# MCU.net
KiCad netlist of a schematic drawn in Altium Designer
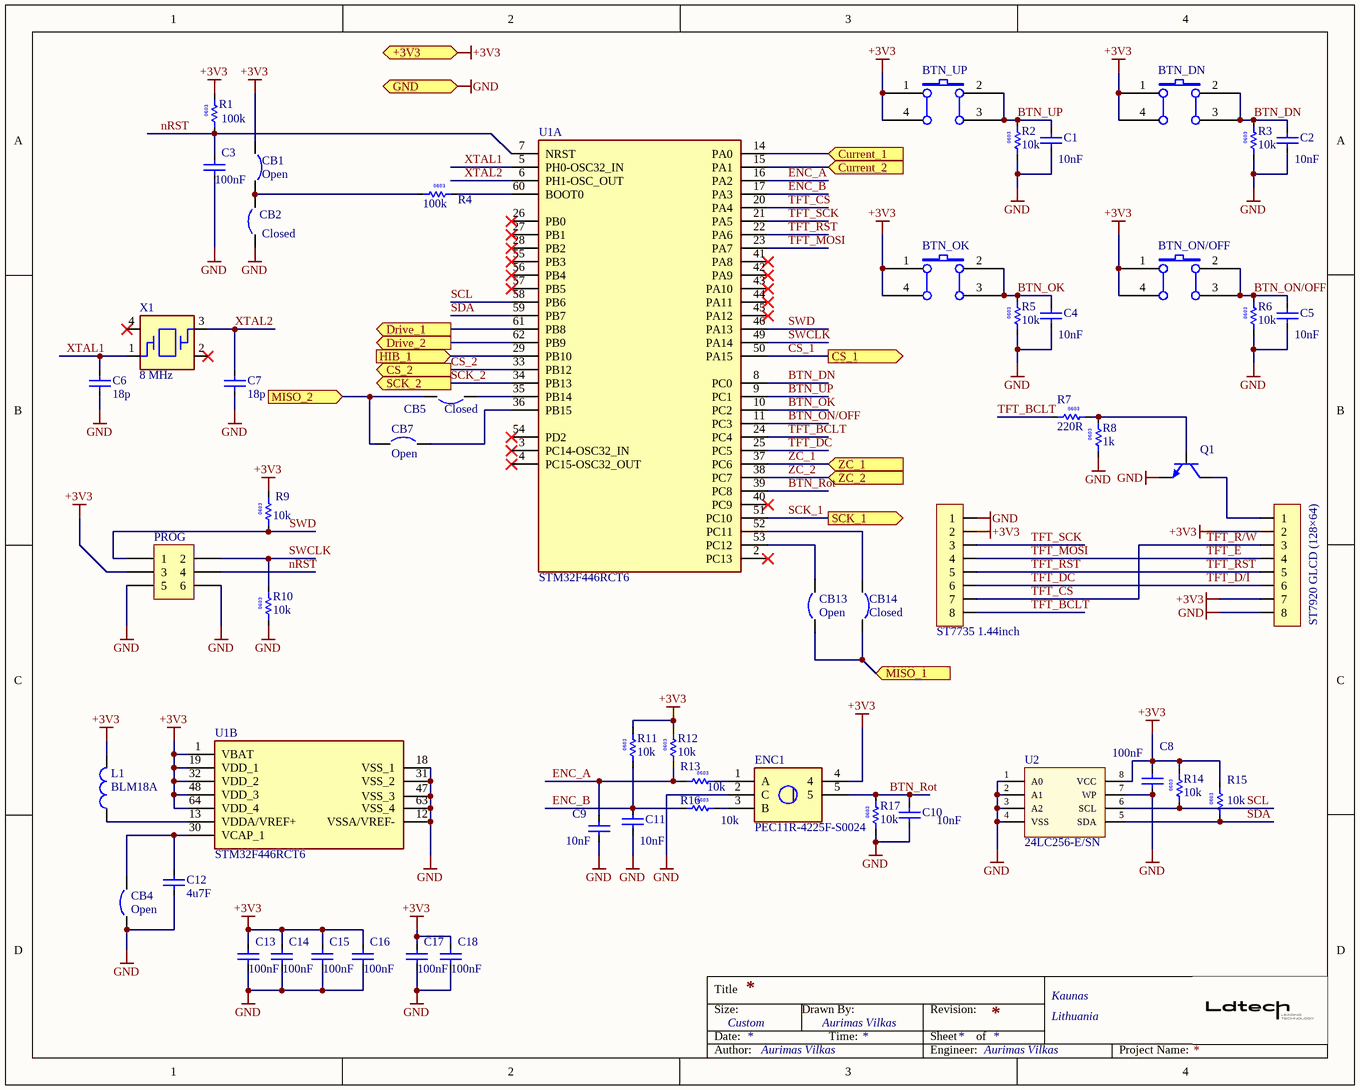
[diagram p0: MCU.SchDoc]

(export (version "E")
  (design (tool "Eeschema 10.0.6"))
  (components
    (comp (ref "BTN_DN")
      (value "Button")
      (footprint "PB-6X6mm")
      (description "FSM2JRT -  Tactile Switch, Non Illuminated, 24 V, 50 mA, 225 gf, PC Pin, FSM Series")
      (libsource (lib "AV_Lib_200418") (part "Tactile PB"))
    )
    (comp (ref "BTN_OK")
      (value "Button")
      (footprint "PB-6X6mm")
      (description "FSM2JRT -  Tactile Switch, Non Illuminated, 24 V, 50 mA, 225 gf, PC Pin, FSM Series")
      (libsource (lib "AV_Lib_200418") (part "Tactile PB"))
    )
    (comp (ref "BTN_ON/OFF")
      (value "Button")
      (footprint "PB-6X6mm")
      (description "FSM2JRT -  Tactile Switch, Non Illuminated, 24 V, 50 mA, 225 gf, PC Pin, FSM Series")
      (libsource (lib "AV_Lib_200418") (part "Tactile PB"))
    )
    (comp (ref "BTN_UP")
      (value "Button")
      (footprint "PB-6X6mm")
      (description "FSM2JRT -  Tactile Switch, Non Illuminated, 24 V, 50 mA, 225 gf, PC Pin, FSM Series")
      (libsource (lib "AV_Lib_200418") (part "Tactile PB"))
    )
    (comp (ref "C1") (value "10nF") (footprint "CAPC1608N") (libsource (lib "DB") (part "C_SM")))
    (comp (ref "C2") (value "10nF") (footprint "CAPC1608N") (libsource (lib "DB") (part "C_SM")))
    (comp (ref "C3") (value "100nF") (footprint "CAPC1608N") (libsource (lib "DB") (part "C_SM")))
    (comp (ref "C4") (value "10nF") (footprint "CAPC1608N") (libsource (lib "DB") (part "C_SM")))
    (comp (ref "C5") (value "10nF") (footprint "CAPC1608N") (libsource (lib "DB") (part "C_SM")))
    (comp (ref "C6") (value "18p") (footprint "CAPC1608N") (libsource (lib "DB") (part "C_SM")))
    (comp (ref "C7") (value "18p") (footprint "CAPC1608N") (libsource (lib "DB") (part "C_SM")))
    (comp (ref "C8") (value "100nF") (footprint "CAPC1608N") (libsource (lib "DB") (part "C_SM")))
    (comp (ref "C9") (value "10nF") (footprint "CAPC1608N") (libsource (lib "DB") (part "C_SM")))
    (comp (ref "C10") (value "10nF") (footprint "CAPC1608N") (libsource (lib "DB") (part "C_SM")))
    (comp (ref "C11") (value "10nF") (footprint "CAPC1608N") (libsource (lib "DB") (part "C_SM")))
    (comp (ref "C12") (value "4u7F") (footprint "CAPC1608N") (libsource (lib "DB") (part "C_SM")))
    (comp (ref "C13") (value "100nF") (footprint "CAPC1608N") (libsource (lib "DB") (part "C_SM")))
    (comp (ref "C14") (value "100nF") (footprint "CAPC1608N") (libsource (lib "DB") (part "C_SM")))
    (comp (ref "C15") (value "100nF") (footprint "CAPC1608N") (libsource (lib "DB") (part "C_SM")))
    (comp (ref "C16") (value "100nF") (footprint "CAPC1608N") (libsource (lib "DB") (part "C_SM")))
    (comp (ref "C17") (value "100nF") (footprint "CAPC1608N") (libsource (lib "DB") (part "C_SM")))
    (comp (ref "C18") (value "100nF") (footprint "CAPC1608N") (libsource (lib "DB") (part "C_SM")))
    (comp (ref "CB1")
      (value "Open")
      (footprint "CB_0603")
      (description "Circuit Breaker")
      (libsource (lib "AV_Lib_200418") (part "CB Open"))
    )
    (comp (ref "CB2")
      (value "Closed")
      (footprint "CB_0603")
      (description "Circuit Breaker")
      (libsource (lib "AV_Lib_200418") (part "CB Closed"))
    )
    (comp (ref "CB4")
      (value "Open")
      (footprint "CB_0603")
      (description "Circuit Breaker")
      (libsource (lib "AV_Lib_200418") (part "CB Open"))
    )
    (comp (ref "CB5")
      (value "Closed")
      (footprint "CB_0603")
      (description "Circuit Breaker")
      (libsource (lib "AV_Lib_200418") (part "CB Closed"))
    )
    (comp (ref "CB7")
      (value "Open")
      (footprint "CB_0603")
      (description "Circuit Breaker")
      (libsource (lib "AV_Lib_200418") (part "CB Open"))
    )
    (comp (ref "CB13")
      (value "Open")
      (footprint "CB_0603")
      (description "Circuit Breaker")
      (libsource (lib "AV_Lib_200418") (part "CB Open"))
    )
    (comp (ref "CB14")
      (value "Closed")
      (footprint "CB_0603")
      (description "Circuit Breaker")
      (libsource (lib "AV_Lib_200418") (part "CB Closed"))
    )
    (comp (ref "ENC1")
      (value "PEC11R-4225F-S0024")
      (footprint "PEC12R-4XXXF-SXXXX_1")
      (libsource (lib "AV_Lib_200418") (part "PEC11R-4225F-S0024"))
    )
    (comp (ref "L1")
      (value "BLM18A")
      (footprint "0603L")
      (libsource (lib "AV_Lib_200418") (part "BLM18AG601SN1D"))
    )
    (comp (ref "PROG")
      (value "PROG")
      (footprint "B6B_SMT")
      (libsource (lib "AV_Lib_200418") (part "B6B_SMT"))
    )
    (comp (ref "Q1")
      (value "FMMT493ATA")
      (footprint "SOT23-3")
      (description "FMMT493ATA -  Bipolar (BJT) Single Transistor, NPN, 60 V, 150 MHz, 500 mW, 1 A, 300 hFE")
      (libsource (lib "AV_Lib_200418") (part "FMMT493ATA"))
    )
    (comp (ref "R1") (value "100k") (footprint "RESC1608N") (libsource (lib "DB") (part "R0603")))
    (comp (ref "R2") (value "10k") (footprint "RESC1608N") (libsource (lib "DB") (part "R0603")))
    (comp (ref "R3") (value "10k") (footprint "RESC1608N") (libsource (lib "DB") (part "R0603")))
    (comp (ref "R4") (value "100k") (footprint "RESC1608N") (libsource (lib "DB") (part "R0603")))
    (comp (ref "R5") (value "10k") (footprint "RESC1608N") (libsource (lib "DB") (part "R0603")))
    (comp (ref "R6") (value "10k") (footprint "RESC1608N") (libsource (lib "DB") (part "R0603")))
    (comp (ref "R7") (value "220R") (footprint "RESC1608N") (libsource (lib "DB") (part "R0603")))
    (comp (ref "R8") (value "1k") (footprint "RESC1608N") (libsource (lib "DB") (part "R0603")))
    (comp (ref "R9") (value "10k") (footprint "RESC1608N") (libsource (lib "DB") (part "R0603")))
    (comp (ref "R10") (value "10k") (footprint "RESC1608N") (libsource (lib "DB") (part "R0603")))
    (comp (ref "R11") (value "10k") (footprint "RESC1608N") (libsource (lib "DB") (part "R0603")))
    (comp (ref "R12") (value "10k") (footprint "RESC1608N") (libsource (lib "DB") (part "R0603")))
    (comp (ref "R13") (value "10k") (footprint "RESC1608N") (libsource (lib "DB") (part "R0603")))
    (comp (ref "R14") (value "10k") (footprint "RESC1608N") (libsource (lib "DB") (part "R0603")))
    (comp (ref "R15") (value "10k") (footprint "RESC1608N") (libsource (lib "DB") (part "R0603")))
    (comp (ref "R16") (value "10k") (footprint "RESC1608N") (libsource (lib "DB") (part "R0603")))
    (comp (ref "R17") (value "10k") (footprint "RESC1608N") (libsource (lib "DB") (part "R0603")))
    (comp (ref "ST7735 1.44inch")
      (value "ST7735 1.44inch")
      (footprint "B8B-XH-A (LF)(SN)")
      (libsource (lib "") (part "B8B-XH-A_1"))
    )
    (comp (ref "ST7920 GLCD (128×64)")
      (value "ST7920 GLCD (128×64)")
      (footprint "B8B-XH-A (LF)(SN)")
      (libsource (lib "AV_Lib_200418") (part "B8B-XH-A"))
    )
    (comp (ref "U1")
      (value "STM32F446RCT6")
      (footprint "LQFP-64N")
      (libsource (lib "AV_Lib_200418") (part "STM32F446RCT6TR"))
    )
    (comp (ref "U2")
      (value "24LC256-E/SN")
      (footprint "SOIC-8")
      (description "24LC256-E/SN -  EEPROM, 256 Kbit, 32K x 8bit, Serial I2C (2-Wire), 400 kHz, SOIC, 8 Pins")
      (libsource (lib "AV_Lib_200418") (part "24LC256-E/SN"))
    )
    (comp (ref "X1")
      (value "8 MHz")
      (footprint "2SMX-3SMXB")
      (description "CRYSTAL, 8M, 18PF CL, 6X3.6MM SMT")
      (libsource (lib "DB") (part "XTAL2"))
    )
  )
  (nets
    (net (code "1") (name "+3V3") (class "Default")
      (node (ref "BTN_DN") (pin "1") (pinfunction "A0_1") (pintype "passive"))
      (node (ref "BTN_DN") (pin "4") (pinfunction "A1_4") (pintype "passive"))
      (node (ref "BTN_OK") (pin "1") (pinfunction "A0_1") (pintype "passive"))
      (node (ref "BTN_OK") (pin "4") (pinfunction "A1_4") (pintype "passive"))
      (node (ref "BTN_ON/OFF") (pin "1") (pinfunction "A0_1") (pintype "passive"))
      (node (ref "BTN_ON/OFF") (pin "4") (pinfunction "A1_4") (pintype "passive"))
      (node (ref "BTN_UP") (pin "1") (pinfunction "A0_1") (pintype "passive"))
      (node (ref "BTN_UP") (pin "4") (pinfunction "A1_4") (pintype "passive"))
      (node (ref "C13") (pin "2") (pinfunction "2_2") (pintype "passive"))
      (node (ref "C14") (pin "2") (pinfunction "2_2") (pintype "passive"))
      (node (ref "C15") (pin "2") (pinfunction "2_2") (pintype "passive"))
      (node (ref "C16") (pin "2") (pinfunction "2_2") (pintype "passive"))
      (node (ref "C17") (pin "2") (pinfunction "2_2") (pintype "passive"))
      (node (ref "C18") (pin "2") (pinfunction "2_2") (pintype "passive"))
      (node (ref "C8") (pin "2") (pinfunction "2_2") (pintype "passive"))
      (node (ref "CB1") (pin "1") (pinfunction "1_1") (pintype "passive"))
      (node (ref "ENC1") (pin "4") (pinfunction "4_4") (pintype "passive"))
      (node (ref "L1") (pin "2") (pinfunction "2_2") (pintype "passive"))
      (node (ref "PROG") (pin "3") (pinfunction "3_3") (pintype "passive"))
      (node (ref "R1") (pin "2") (pinfunction "2_2") (pintype "passive"))
      (node (ref "R11") (pin "2") (pinfunction "2_2") (pintype "passive"))
      (node (ref "R12") (pin "2") (pinfunction "2_2") (pintype "passive"))
      (node (ref "R14") (pin "2") (pinfunction "2_2") (pintype "passive"))
      (node (ref "R15") (pin "2") (pinfunction "2_2") (pintype "passive"))
      (node (ref "R9") (pin "2") (pinfunction "2_2") (pintype "passive"))
      (node (ref "ST7735 1.44inch") (pin "2") (pinfunction "2_2") (pintype "passive"))
      (node (ref "ST7920 GLCD (128×64)") (pin "2") (pinfunction "2_2") (pintype "passive"))
      (node (ref "ST7920 GLCD (128×64)") (pin "7") (pinfunction "7_7") (pintype "passive"))
      (node (ref "U1") (pin "1") (pinfunction "VBAT_1") (pintype "passive"))
      (node (ref "U1") (pin "19") (pinfunction "VDD_1_19") (pintype "passive"))
      (node (ref "U1") (pin "32") (pinfunction "VDD_2_32") (pintype "passive"))
      (node (ref "U1") (pin "48") (pinfunction "VDD_3_48") (pintype "passive"))
      (node (ref "U1") (pin "64") (pinfunction "VDD_4_64") (pintype "passive"))
      (node (ref "U2") (pin "8") (pinfunction "VCC_8") (pintype "passive"))
    )
    (net (code "2") (name "/BTN_DN") (class "Default")
      (node (ref "BTN_DN") (pin "2") (pinfunction "B0_2") (pintype "passive"))
      (node (ref "BTN_DN") (pin "3") (pinfunction "B1_3") (pintype "passive"))
      (node (ref "C2") (pin "1") (pinfunction "1_1") (pintype "passive"))
      (node (ref "R3") (pin "2") (pinfunction "2_2") (pintype "passive"))
      (node (ref "U1") (pin "8") (pinfunction "PC0_8") (pintype "passive"))
    )
    (net (code "3") (name "/BTN_OK") (class "Default")
      (node (ref "BTN_OK") (pin "2") (pinfunction "B0_2") (pintype "passive"))
      (node (ref "BTN_OK") (pin "3") (pinfunction "B1_3") (pintype "passive"))
      (node (ref "C4") (pin "1") (pinfunction "1_1") (pintype "passive"))
      (node (ref "R5") (pin "2") (pinfunction "2_2") (pintype "passive"))
      (node (ref "U1") (pin "10") (pinfunction "PC2_10") (pintype "passive"))
    )
    (net (code "4") (name "/BTN_ON{slash}OFF") (class "Default")
      (node (ref "BTN_ON/OFF") (pin "2") (pinfunction "B0_2") (pintype "passive"))
      (node (ref "BTN_ON/OFF") (pin "3") (pinfunction "B1_3") (pintype "passive"))
      (node (ref "C5") (pin "1") (pinfunction "1_1") (pintype "passive"))
      (node (ref "R6") (pin "2") (pinfunction "2_2") (pintype "passive"))
      (node (ref "U1") (pin "11") (pinfunction "PC3_11") (pintype "passive"))
    )
    (net (code "5") (name "/BTN_Rot") (class "Default")
      (node (ref "C10") (pin "1") (pinfunction "1_1") (pintype "passive"))
      (node (ref "ENC1") (pin "5") (pinfunction "5_5") (pintype "passive"))
      (node (ref "R17") (pin "2") (pinfunction "2_2") (pintype "passive"))
      (node (ref "U1") (pin "39") (pinfunction "PC8_39") (pintype "passive"))
    )
    (net (code "6") (name "/BTN_UP") (class "Default")
      (node (ref "BTN_UP") (pin "2") (pinfunction "B0_2") (pintype "passive"))
      (node (ref "BTN_UP") (pin "3") (pinfunction "B1_3") (pintype "passive"))
      (node (ref "C1") (pin "1") (pinfunction "1_1") (pintype "passive"))
      (node (ref "R2") (pin "2") (pinfunction "2_2") (pintype "passive"))
      (node (ref "U1") (pin "9") (pinfunction "PC1_9") (pintype "passive"))
    )
    (net (code "7") (name "/CS_1") (class "Default")
      (node (ref "U1") (pin "50") (pinfunction "PA15_50") (pintype "passive"))
    )
    (net (code "8") (name "/CS_2") (class "Default")
      (node (ref "U1") (pin "33") (pinfunction "PB12_33") (pintype "passive"))
    )
    (net (code "9") (name "/Current_1") (class "Default")
      (node (ref "U1") (pin "14") (pinfunction "PA0_14") (pintype "passive"))
    )
    (net (code "10") (name "/Current_2") (class "Default")
      (node (ref "U1") (pin "15") (pinfunction "PA1_15") (pintype "passive"))
    )
    (net (code "11") (name "/Drive_1") (class "Default")
      (node (ref "U1") (pin "61") (pinfunction "PB8_61") (pintype "passive"))
    )
    (net (code "12") (name "/Drive_2") (class "Default")
      (node (ref "U1") (pin "62") (pinfunction "PB9_62") (pintype "passive"))
    )
    (net (code "13") (name "/ENC_A") (class "Default")
      (node (ref "C9") (pin "1") (pinfunction "1_1") (pintype "passive"))
      (node (ref "R12") (pin "1") (pinfunction "1_1") (pintype "passive"))
      (node (ref "R13") (pin "1") (pinfunction "1_1") (pintype "passive"))
      (node (ref "U1") (pin "16") (pinfunction "PA2_16") (pintype "passive"))
    )
    (net (code "14") (name "/ENC_B") (class "Default")
      (node (ref "C11") (pin "1") (pinfunction "1_1") (pintype "passive"))
      (node (ref "R11") (pin "1") (pinfunction "1_1") (pintype "passive"))
      (node (ref "R16") (pin "1") (pinfunction "1_1") (pintype "passive"))
      (node (ref "U1") (pin "17") (pinfunction "PA3_17") (pintype "passive"))
    )
    (net (code "15") (name "/HIB_1") (class "Default")
      (node (ref "U1") (pin "29") (pinfunction "PB10_29") (pintype "passive"))
    )
    (net (code "16") (name "/MISO_1") (class "Default")
      (node (ref "CB13") (pin "1") (pinfunction "1_1") (pintype "passive"))
      (node (ref "CB14") (pin "2") (pinfunction "2_2") (pintype "passive"))
    )
    (net (code "17") (name "/MISO_2") (class "Default")
      (node (ref "CB5") (pin "2") (pinfunction "2_2") (pintype "passive"))
      (node (ref "CB7") (pin "1") (pinfunction "1_1") (pintype "passive"))
    )
    (net (code "18") (name "/SCK_1") (class "Default")
      (node (ref "U1") (pin "51") (pinfunction "PC10_51") (pintype "passive"))
    )
    (net (code "19") (name "/SCK_2") (class "Default")
      (node (ref "U1") (pin "34") (pinfunction "PB13_34") (pintype "passive"))
    )
    (net (code "20") (name "/SCL") (class "Default")
      (node (ref "R14") (pin "1") (pinfunction "1_1") (pintype "passive"))
      (node (ref "U1") (pin "58") (pinfunction "PB6_58") (pintype "passive"))
      (node (ref "U2") (pin "6") (pinfunction "SCL_6") (pintype "passive"))
    )
    (net (code "21") (name "/SDA") (class "Default")
      (node (ref "R15") (pin "1") (pinfunction "1_1") (pintype "passive"))
      (node (ref "U1") (pin "59") (pinfunction "PB7_59") (pintype "passive"))
      (node (ref "U2") (pin "5") (pinfunction "SDA_5") (pintype "passive"))
    )
    (net (code "22") (name "/SWCLK") (class "Default")
      (node (ref "PROG") (pin "2") (pinfunction "2_2") (pintype "passive"))
      (node (ref "R10") (pin "2") (pinfunction "2_2") (pintype "passive"))
      (node (ref "U1") (pin "49") (pinfunction "PA14_49") (pintype "passive"))
    )
    (net (code "23") (name "/SWD") (class "Default")
      (node (ref "PROG") (pin "1") (pinfunction "1_1") (pintype "passive"))
      (node (ref "R9") (pin "1") (pinfunction "1_1") (pintype "passive"))
      (node (ref "U1") (pin "46") (pinfunction "PA13_46") (pintype "passive"))
    )
    (net (code "24") (name "/TFT_BCLT") (class "Default")
      (node (ref "R7") (pin "1") (pinfunction "1_1") (pintype "passive"))
      (node (ref "ST7735 1.44inch") (pin "8") (pinfunction "8_8") (pintype "passive"))
      (node (ref "U1") (pin "24") (pinfunction "PC4_24") (pintype "passive"))
    )
    (net (code "25") (name "/TFT_CS") (class "Default")
      (node (ref "ST7735 1.44inch") (pin "7") (pinfunction "7_7") (pintype "passive"))
      (node (ref "ST7920 GLCD (128×64)") (pin "3") (pinfunction "3_3") (pintype "passive"))
      (node (ref "U1") (pin "20") (pinfunction "PA4_20") (pintype "passive"))
    )
    (net (code "26") (name "/TFT_DC") (class "Default")
      (node (ref "ST7735 1.44inch") (pin "6") (pinfunction "6_6") (pintype "passive"))
      (node (ref "ST7920 GLCD (128×64)") (pin "6") (pinfunction "6_6") (pintype "passive"))
      (node (ref "U1") (pin "25") (pinfunction "PC5_25") (pintype "passive"))
    )
    (net (code "27") (name "/TFT_E") (class "Default")
      (node (ref "ST7735 1.44inch") (pin "4") (pinfunction "4_4") (pintype "passive"))
      (node (ref "ST7920 GLCD (128×64)") (pin "4") (pinfunction "4_4") (pintype "passive"))
      (node (ref "U1") (pin "23") (pinfunction "PA7_23") (pintype "passive"))
    )
    (net (code "28") (name "/TFT_RST") (class "Default")
      (node (ref "ST7735 1.44inch") (pin "5") (pinfunction "5_5") (pintype "passive"))
      (node (ref "ST7920 GLCD (128×64)") (pin "5") (pinfunction "5_5") (pintype "passive"))
      (node (ref "U1") (pin "22") (pinfunction "PA6_22") (pintype "passive"))
    )
    (net (code "29") (name "/TFT_SCK") (class "Default")
      (node (ref "ST7735 1.44inch") (pin "3") (pinfunction "3_3") (pintype "passive"))
      (node (ref "U1") (pin "21") (pinfunction "PA5_21") (pintype "passive"))
    )
    (net (code "30") (name "/XTAL1") (class "Default")
      (node (ref "C6") (pin "2") (pinfunction "2_2") (pintype "passive"))
      (node (ref "U1") (pin "5") (pinfunction "PH0-OSC32_IN_5") (pintype "passive"))
      (node (ref "X1") (pin "1") (pinfunction "1_1") (pintype "passive"))
    )
    (net (code "31") (name "/XTAL2") (class "Default")
      (node (ref "C7") (pin "2") (pinfunction "2_2") (pintype "passive"))
      (node (ref "U1") (pin "6") (pinfunction "PH1-OSC_OUT_6") (pintype "passive"))
      (node (ref "X1") (pin "3") (pinfunction "3_3") (pintype "passive"))
    )
    (net (code "32") (name "/ZC_1") (class "Default")
      (node (ref "U1") (pin "37") (pinfunction "PC6_37") (pintype "passive"))
    )
    (net (code "33") (name "/ZC_2") (class "Default")
      (node (ref "U1") (pin "38") (pinfunction "PC7_38") (pintype "passive"))
    )
    (net (code "34") (name "/nRST") (class "Default")
      (node (ref "C3") (pin "2") (pinfunction "2_2") (pintype "passive"))
      (node (ref "PROG") (pin "4") (pinfunction "4_4") (pintype "passive"))
      (node (ref "R1") (pin "1") (pinfunction "1_1") (pintype "passive"))
      (node (ref "U1") (pin "7") (pinfunction "NRST_7") (pintype "passive"))
    )
    (net (code "35") (name "GND") (class "Default")
      (node (ref "C1") (pin "2") (pinfunction "2_2") (pintype "passive"))
      (node (ref "C10") (pin "2") (pinfunction "2_2") (pintype "passive"))
      (node (ref "C11") (pin "2") (pinfunction "2_2") (pintype "passive"))
      (node (ref "C12") (pin "1") (pinfunction "1_1") (pintype "passive"))
      (node (ref "C13") (pin "1") (pinfunction "1_1") (pintype "passive"))
      (node (ref "C14") (pin "1") (pinfunction "1_1") (pintype "passive"))
      (node (ref "C15") (pin "1") (pinfunction "1_1") (pintype "passive"))
      (node (ref "C16") (pin "1") (pinfunction "1_1") (pintype "passive"))
      (node (ref "C17") (pin "1") (pinfunction "1_1") (pintype "passive"))
      (node (ref "C18") (pin "1") (pinfunction "1_1") (pintype "passive"))
      (node (ref "C2") (pin "2") (pinfunction "2_2") (pintype "passive"))
      (node (ref "C3") (pin "1") (pinfunction "1_1") (pintype "passive"))
      (node (ref "C4") (pin "2") (pinfunction "2_2") (pintype "passive"))
      (node (ref "C5") (pin "2") (pinfunction "2_2") (pintype "passive"))
      (node (ref "C6") (pin "1") (pinfunction "1_1") (pintype "passive"))
      (node (ref "C7") (pin "1") (pinfunction "1_1") (pintype "passive"))
      (node (ref "C8") (pin "1") (pinfunction "1_1") (pintype "passive"))
      (node (ref "C9") (pin "2") (pinfunction "2_2") (pintype "passive"))
      (node (ref "CB2") (pin "1") (pinfunction "1_1") (pintype "passive"))
      (node (ref "CB4") (pin "1") (pinfunction "1_1") (pintype "passive"))
      (node (ref "ENC1") (pin "2") (pinfunction "C_2") (pintype "passive"))
      (node (ref "PROG") (pin "5") (pinfunction "5_5") (pintype "passive"))
      (node (ref "PROG") (pin "6") (pinfunction "6_6") (pintype "passive"))
      (node (ref "Q1") (pin "2") (pinfunction "E_2") (pintype "passive"))
      (node (ref "R10") (pin "1") (pinfunction "1_1") (pintype "passive"))
      (node (ref "R17") (pin "1") (pinfunction "1_1") (pintype "passive"))
      (node (ref "R2") (pin "1") (pinfunction "1_1") (pintype "passive"))
      (node (ref "R3") (pin "1") (pinfunction "1_1") (pintype "passive"))
      (node (ref "R5") (pin "1") (pinfunction "1_1") (pintype "passive"))
      (node (ref "R6") (pin "1") (pinfunction "1_1") (pintype "passive"))
      (node (ref "R8") (pin "1") (pinfunction "1_1") (pintype "passive"))
      (node (ref "ST7735 1.44inch") (pin "1") (pinfunction "1_1") (pintype "passive"))
      (node (ref "ST7920 GLCD (128×64)") (pin "8") (pinfunction "8_8") (pintype "passive"))
      (node (ref "U1") (pin "12") (pinfunction "VSSA/VREF-_12") (pintype "passive"))
      (node (ref "U1") (pin "18") (pinfunction "VSS_1_18") (pintype "passive"))
      (node (ref "U1") (pin "31") (pinfunction "VSS_2_31") (pintype "passive"))
      (node (ref "U1") (pin "47") (pinfunction "VSS_3_47") (pintype "passive"))
      (node (ref "U1") (pin "63") (pinfunction "VSS_4_63") (pintype "passive"))
      (node (ref "U2") (pin "1") (pinfunction "A0_1") (pintype "passive"))
      (node (ref "U2") (pin "2") (pinfunction "A1_2") (pintype "passive"))
      (node (ref "U2") (pin "3") (pinfunction "A2_3") (pintype "passive"))
      (node (ref "U2") (pin "4") (pinfunction "VSS_4") (pintype "passive"))
      (node (ref "U2") (pin "7") (pinfunction "WP_7") (pintype "passive"))
    )
    (net (code "36") (name "Net-(CB1-Pad2)") (class "Default")
      (node (ref "CB1") (pin "2") (pinfunction "2_2") (pintype "passive"))
      (node (ref "CB2") (pin "2") (pinfunction "2_2") (pintype "passive"))
      (node (ref "R4") (pin "1") (pinfunction "1_1") (pintype "passive"))
    )
    (net (code "37") (name "Net-(ENC1-A)") (class "Default")
      (node (ref "ENC1") (pin "1") (pinfunction "A_1") (pintype "passive"))
      (node (ref "R13") (pin "2") (pinfunction "2_2") (pintype "passive"))
    )
    (net (code "38") (name "Net-(ENC1-B)") (class "Default")
      (node (ref "ENC1") (pin "3") (pinfunction "B_3") (pintype "passive"))
      (node (ref "R16") (pin "2") (pinfunction "2_2") (pintype "passive"))
    )
    (net (code "39") (name "Net-(Q1-B)") (class "Default")
      (node (ref "Q1") (pin "1") (pinfunction "B_1") (pintype "passive"))
      (node (ref "R7") (pin "2") (pinfunction "2_2") (pintype "passive"))
      (node (ref "R8") (pin "2") (pinfunction "2_2") (pintype "passive"))
    )
    (net (code "40") (name "Net-(Q1-C)") (class "Default")
      (node (ref "Q1") (pin "3") (pinfunction "C_3") (pintype "passive"))
      (node (ref "ST7920 GLCD (128×64)") (pin "1") (pinfunction "1_1") (pintype "passive"))
    )
    (net (code "41") (name "Net-(U1A-BOOT0)") (class "Default")
      (node (ref "R4") (pin "2") (pinfunction "2_2") (pintype "passive"))
      (node (ref "U1") (pin "60") (pinfunction "BOOT0_60") (pintype "passive"))
    )
    (net (code "42") (name "Net-(U1A-PB14)") (class "Default")
      (node (ref "CB5") (pin "1") (pinfunction "1_1") (pintype "passive"))
      (node (ref "U1") (pin "35") (pinfunction "PB14_35") (pintype "passive"))
    )
    (net (code "43") (name "Net-(U1A-PB15)") (class "Default")
      (node (ref "CB7") (pin "2") (pinfunction "2_2") (pintype "passive"))
      (node (ref "U1") (pin "36") (pinfunction "PB15_36") (pintype "passive"))
    )
    (net (code "44") (name "Net-(U1A-PC11)") (class "Default")
      (node (ref "CB14") (pin "1") (pinfunction "1_1") (pintype "passive"))
      (node (ref "U1") (pin "52") (pinfunction "PC11_52") (pintype "passive"))
    )
    (net (code "45") (name "Net-(U1A-PC12)") (class "Default")
      (node (ref "CB13") (pin "2") (pinfunction "2_2") (pintype "passive"))
      (node (ref "U1") (pin "53") (pinfunction "PC12_53") (pintype "passive"))
    )
    (net (code "46") (name "Net-(U1B-VCAP_1)") (class "Default")
      (node (ref "C12") (pin "2") (pinfunction "2_2") (pintype "passive"))
      (node (ref "CB4") (pin "2") (pinfunction "2_2") (pintype "passive"))
      (node (ref "U1") (pin "30") (pinfunction "VCAP_1_30") (pintype "passive"))
    )
    (net (code "47") (name "Net-(U1B-VDDA{slash}VREF+)") (class "Default")
      (node (ref "L1") (pin "1") (pinfunction "1_1") (pintype "passive"))
      (node (ref "U1") (pin "13") (pinfunction "VDDA/VREF+_13") (pintype "passive"))
    )
    (net (code "48") (name "unconnected-(U1A-PA8-Pad41)") (class "Default")
      (node (ref "U1") (pin "41") (pinfunction "PA8_41") (pintype "passive+no_connect"))
    )
    (net (code "49") (name "unconnected-(U1A-PA9-Pad42)") (class "Default")
      (node (ref "U1") (pin "42") (pinfunction "PA9_42") (pintype "passive+no_connect"))
    )
    (net (code "50") (name "unconnected-(U1A-PA10-Pad43)") (class "Default")
      (node (ref "U1") (pin "43") (pinfunction "PA10_43") (pintype "passive+no_connect"))
    )
    (net (code "51") (name "unconnected-(U1A-PA11-Pad44)") (class "Default")
      (node (ref "U1") (pin "44") (pinfunction "PA11_44") (pintype "passive+no_connect"))
    )
    (net (code "52") (name "unconnected-(U1A-PA12-Pad45)") (class "Default")
      (node (ref "U1") (pin "45") (pinfunction "PA12_45") (pintype "passive+no_connect"))
    )
    (net (code "53") (name "unconnected-(U1A-PB0-Pad26)") (class "Default")
      (node (ref "U1") (pin "26") (pinfunction "PB0_26") (pintype "passive+no_connect"))
    )
    (net (code "54") (name "unconnected-(U1A-PB1-Pad27)") (class "Default")
      (node (ref "U1") (pin "27") (pinfunction "PB1_27") (pintype "passive+no_connect"))
    )
    (net (code "55") (name "unconnected-(U1A-PB2-Pad28)") (class "Default")
      (node (ref "U1") (pin "28") (pinfunction "PB2_28") (pintype "passive+no_connect"))
    )
    (net (code "56") (name "unconnected-(U1A-PB3-Pad55)") (class "Default")
      (node (ref "U1") (pin "55") (pinfunction "PB3_55") (pintype "passive+no_connect"))
    )
    (net (code "57") (name "unconnected-(U1A-PB4-Pad56)") (class "Default")
      (node (ref "U1") (pin "56") (pinfunction "PB4_56") (pintype "passive+no_connect"))
    )
    (net (code "58") (name "unconnected-(U1A-PB5-Pad57)") (class "Default")
      (node (ref "U1") (pin "57") (pinfunction "PB5_57") (pintype "passive+no_connect"))
    )
    (net (code "59") (name "unconnected-(U1A-PC9-Pad40)") (class "Default")
      (node (ref "U1") (pin "40") (pinfunction "PC9_40") (pintype "passive+no_connect"))
    )
    (net (code "60") (name "unconnected-(U1A-PC13-Pad2)") (class "Default")
      (node (ref "U1") (pin "2") (pinfunction "PC13_2") (pintype "passive+no_connect"))
    )
    (net (code "61") (name "unconnected-(U1A-PC14-OSC32_IN-Pad3)") (class "Default")
      (node (ref "U1") (pin "3") (pinfunction "PC14-OSC32_IN_3") (pintype "passive+no_connect"))
    )
    (net (code "62") (name "unconnected-(U1A-PC15-OSC32_OUT-Pad4)") (class "Default")
      (node (ref "U1") (pin "4") (pinfunction "PC15-OSC32_OUT_4") (pintype "passive+no_connect"))
    )
    (net (code "63") (name "unconnected-(U1A-PD2-Pad54)") (class "Default")
      (node (ref "U1") (pin "54") (pinfunction "PD2_54") (pintype "passive+no_connect"))
    )
    (net (code "64") (name "unconnected-(X1-Pad2)") (class "Default")
      (node (ref "X1") (pin "2") (pinfunction "2_2") (pintype "passive+no_connect"))
    )
    (net (code "65") (name "unconnected-(X1-Pad4)") (class "Default")
      (node (ref "X1") (pin "4") (pinfunction "4_4") (pintype "passive+no_connect"))
    )
  )
)
